# Eagle_USB_JST-XH_Converter.net
KiCad netlist of a schematic drawn in EAGLE
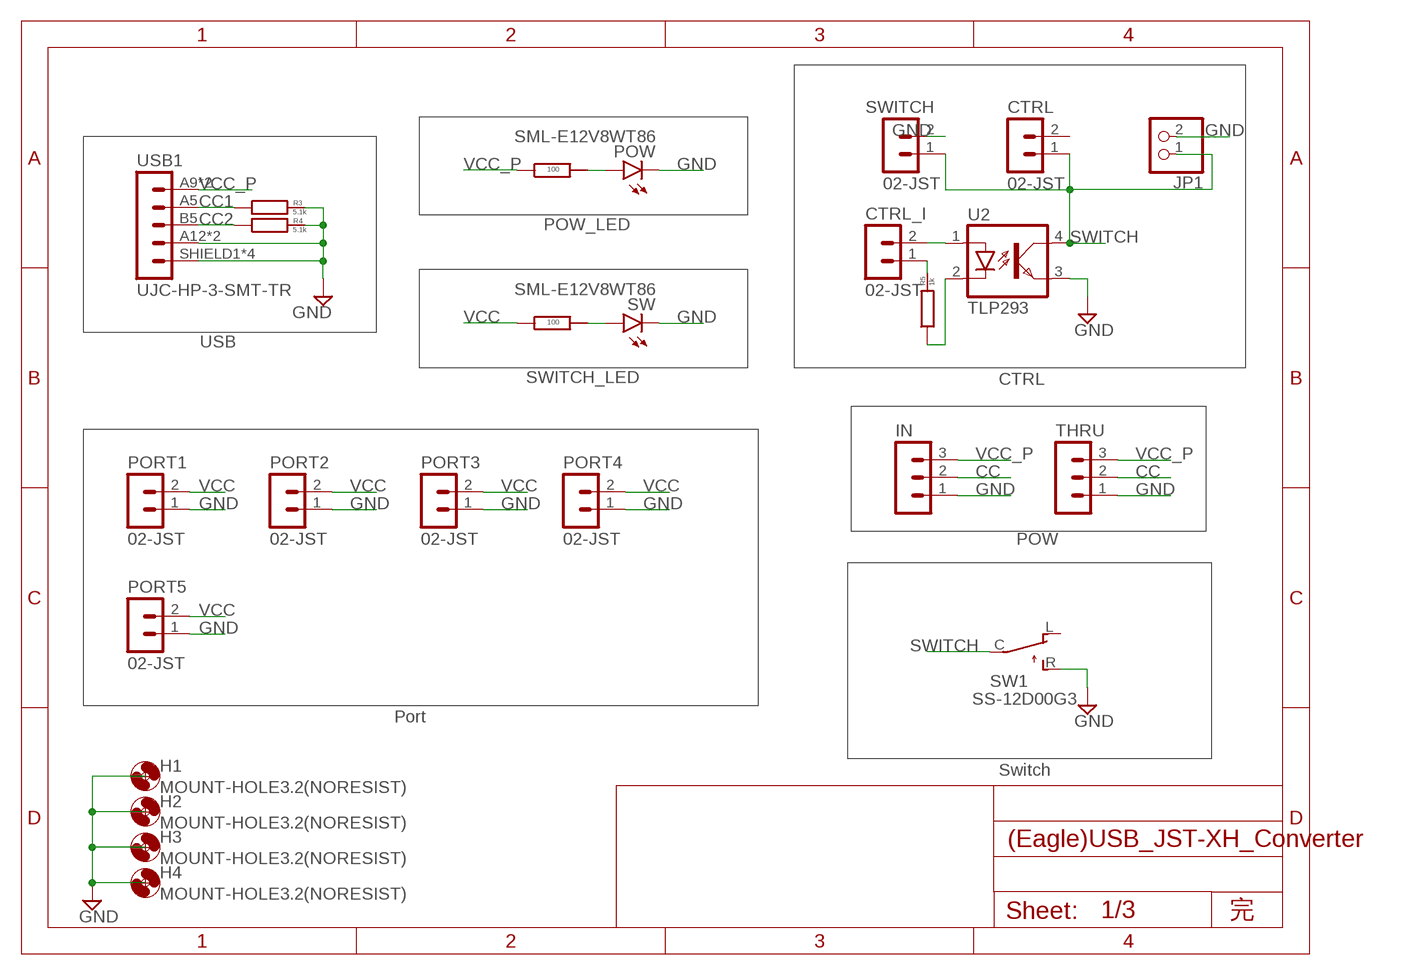
[diagram p0: schematic, sheet 1]
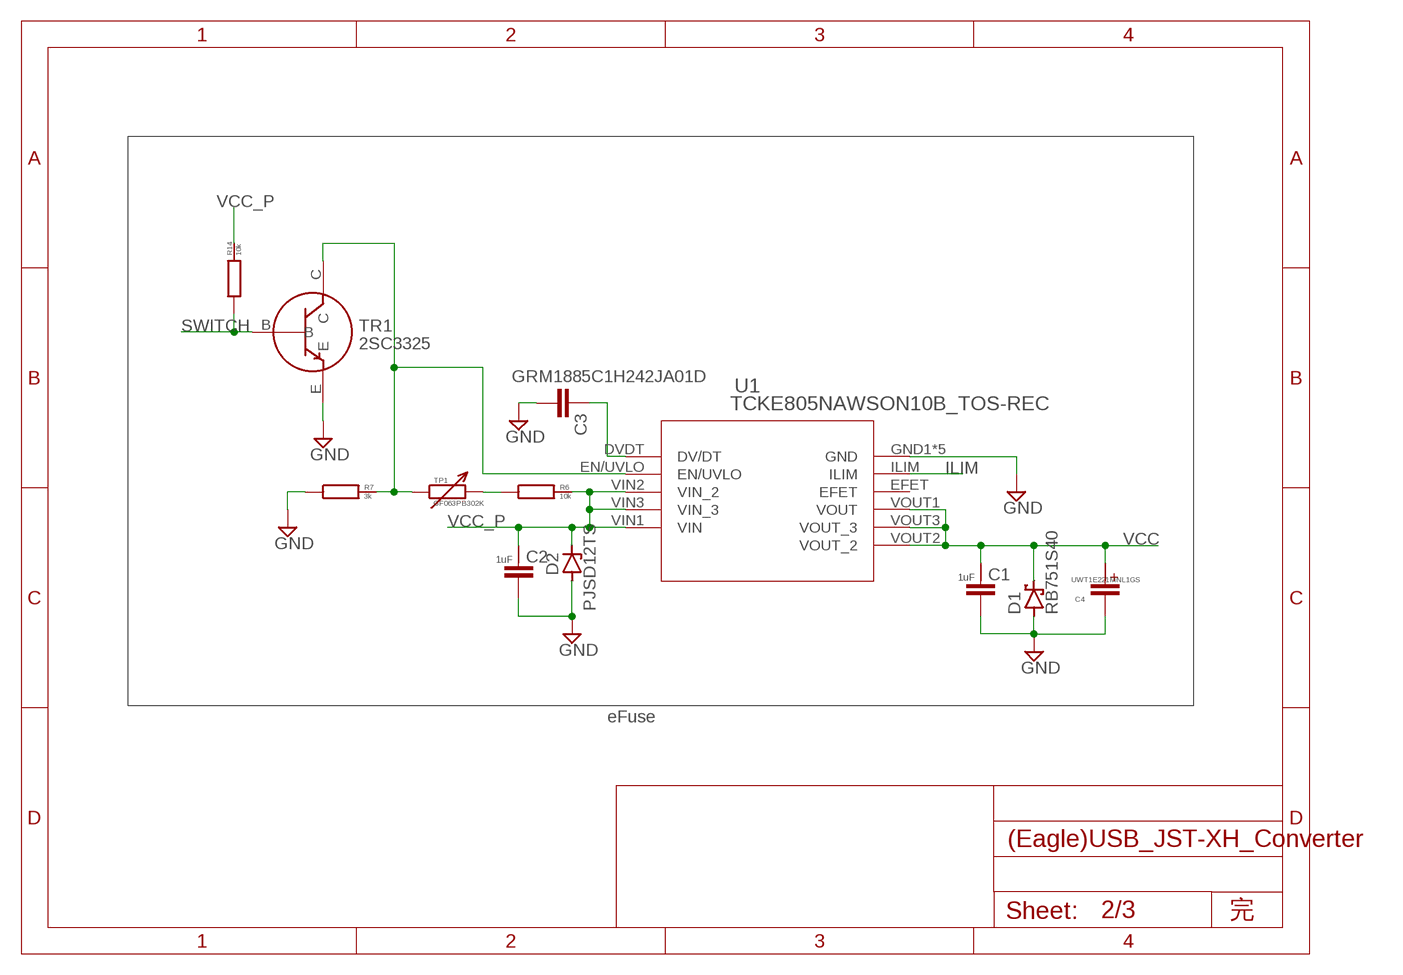
[diagram p1: schematic, sheet 2]
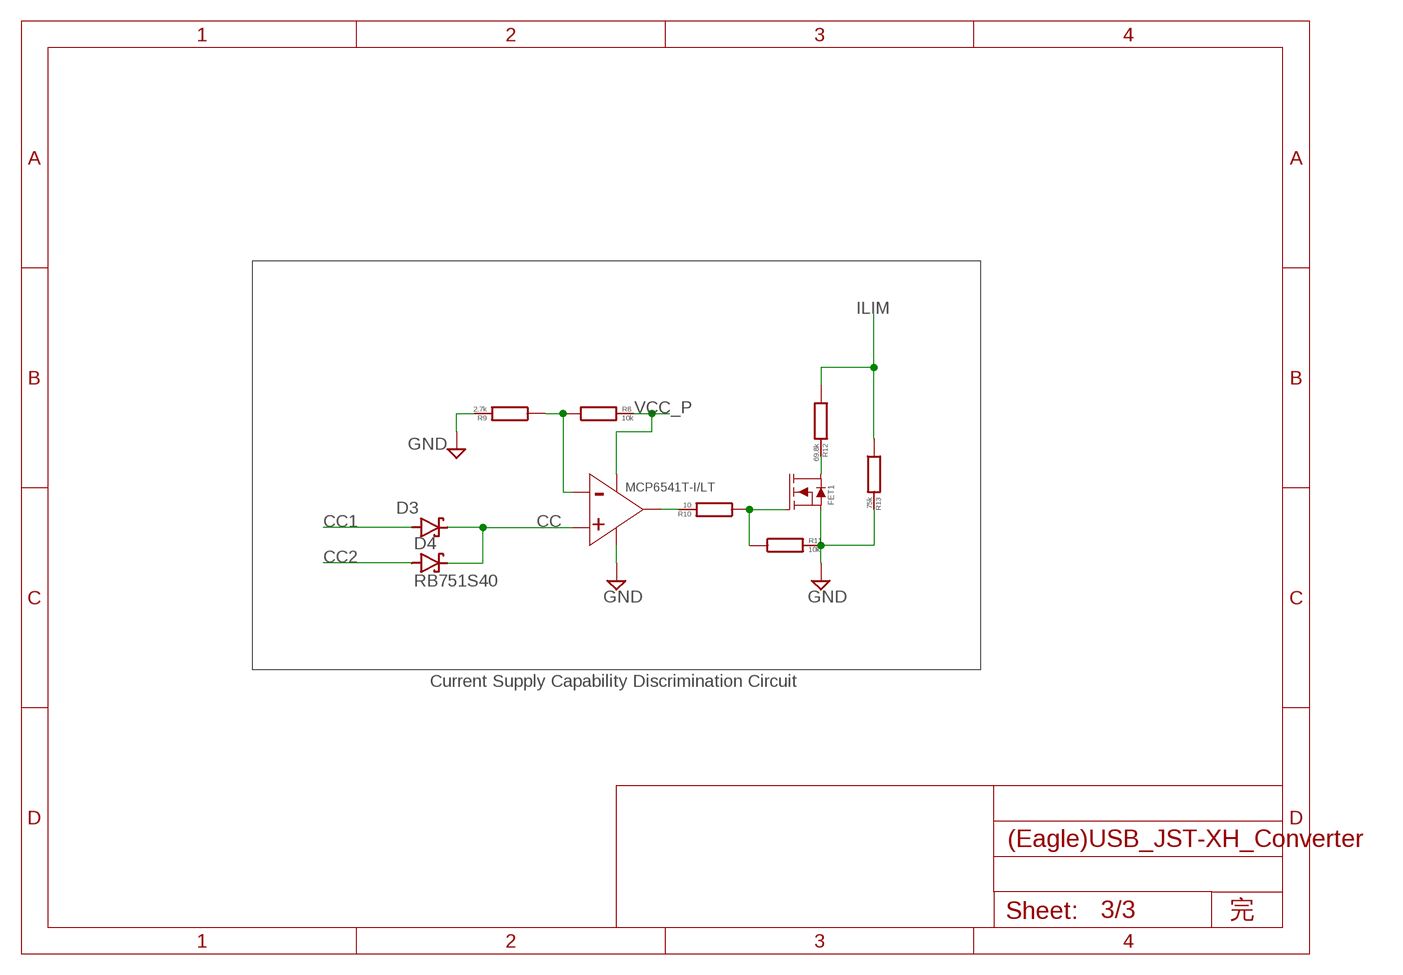
[diagram p2: schematic, sheet 3]

(export (version "E")
  (design (tool "Eeschema 10.0.6"))
  (components
    (comp (ref "COMP1")
      (value "MCP6541T-I/LT")
      (footprint "eagle-import:SC-70-5")
      (libsource (lib "eagle-import") (part "MCP6541T-I/LT"))
    )
    (comp (ref "D3")
      (value "RB751S40")
      (footprint "eagle-import:SOD-523")
      (libsource (lib "eagle-import") (part "RB751S40"))
    )
    (comp (ref "D4")
      (value "RB751S40")
      (footprint "eagle-import:SOD-523")
      (libsource (lib "eagle-import") (part "RB751S40"))
    )
    (comp (ref "FET1")
      (value "BSS138")
      (footprint "eagle-import:SOT-23")
      (libsource (lib "eagle-import") (part "BSS138"))
    )
    (comp (ref "R8")
      (value "10k")
      (footprint "eagle-import:RG2012")
      (libsource (lib "eagle-import") (part "RG2012"))
    )
    (comp (ref "R9")
      (value "2.7k")
      (footprint "eagle-import:RG2012")
      (libsource (lib "eagle-import") (part "RG2012"))
    )
    (comp (ref "R10")
      (value "10")
      (footprint "eagle-import:RG2012")
      (libsource (lib "eagle-import") (part "RG2012"))
    )
    (comp (ref "R11")
      (value "10k")
      (footprint "eagle-import:RG2012")
      (libsource (lib "eagle-import") (part "RG2012"))
    )
    (comp (ref "R12")
      (value "69.8k")
      (footprint "eagle-import:RG2012")
      (libsource (lib "eagle-import") (part "RG2012"))
    )
    (comp (ref "R13")
      (value "75k")
      (footprint "eagle-import:RG2012")
      (libsource (lib "eagle-import") (part "RG2012"))
    )
    (comp (ref "C1")
      (value "GRM21BC72A105KE01")
      (footprint "eagle-import:GRM21BC72A105KE01")
      (libsource (lib "eagle-import") (part "GRM21BC72A105KE01"))
    )
    (comp (ref "C2")
      (value "GRM21BC72A105KE01")
      (footprint "eagle-import:GRM21BC72A105KE01")
      (libsource (lib "eagle-import") (part "GRM21BC72A105KE01"))
    )
    (comp (ref "C3")
      (value "GRM1885C1H242JA01D")
      (footprint "eagle-import:GRM18")
      (libsource (lib "eagle-import") (part "GRM1885C1H242JA01D"))
    )
    (comp (ref "C4")
      (value "UWT1E221MNL1GS")
      (footprint "eagle-import:UWT1E221MNL1GS")
      (libsource (lib "eagle-import") (part "UWT1E221MNL1GS"))
    )
    (comp (ref "D1")
      (value "RB751S40")
      (footprint "eagle-import:SOD-523")
      (libsource (lib "eagle-import") (part "RB751S40"))
    )
    (comp (ref "D2")
      (value "PJSD12TS")
      (footprint "eagle-import:SOD-523")
      (libsource (lib "eagle-import") (part "PJSD12TS"))
    )
    (comp (ref "R6")
      (value "10k")
      (footprint "eagle-import:RG2012")
      (libsource (lib "eagle-import") (part "RG2012"))
    )
    (comp (ref "R7")
      (value "3k")
      (footprint "eagle-import:RG2012")
      (libsource (lib "eagle-import") (part "RG2012"))
    )
    (comp (ref "R14")
      (value "10k")
      (footprint "eagle-import:RG2012")
      (libsource (lib "eagle-import") (part "RG2012"))
    )
    (comp (ref "TP1")
      (value "GF063PB302K")
      (footprint "eagle-import:GF063PB104K")
      (libsource (lib "eagle-import") (part "GF063PB302K"))
    )
    (comp (ref "TR1")
      (value "2SC3325")
      (footprint "eagle-import:2SC3325")
      (libsource (lib "eagle-import") (part "2SC3325"))
    )
    (comp (ref "U1")
      (value "TCKE805NAWSON10B_TOS-REC")
      (footprint "eagle-import:WSON10B_TOS-RIC")
      (libsource (lib "eagle-import") (part "TCKE805NAWSON10B_TOS-REC"))
    )
    (comp (ref "CTRL")
      (value "02-JST")
      (footprint "eagle-import:B2B-XH")
      (libsource (lib "eagle-import") (part "02-JST"))
    )
    (comp (ref "CTRL_I")
      (value "02-JST")
      (footprint "eagle-import:B2B-XH")
      (libsource (lib "eagle-import") (part "02-JST"))
    )
    (comp (ref "H1")
      (value "MOUNT-HOLE3.2(NORESIST)")
      (footprint "eagle-import:3,2")
      (libsource (lib "eagle-import") (part "MOUNT-HOLE3.2(NORESIST)"))
    )
    (comp (ref "H2")
      (value "MOUNT-HOLE3.2(NORESIST)")
      (footprint "eagle-import:3,2")
      (libsource (lib "eagle-import") (part "MOUNT-HOLE3.2(NORESIST)"))
    )
    (comp (ref "H3")
      (value "MOUNT-HOLE3.2(NORESIST)")
      (footprint "eagle-import:3,2")
      (libsource (lib "eagle-import") (part "MOUNT-HOLE3.2(NORESIST)"))
    )
    (comp (ref "H4")
      (value "MOUNT-HOLE3.2(NORESIST)")
      (footprint "eagle-import:3,2")
      (libsource (lib "eagle-import") (part "MOUNT-HOLE3.2(NORESIST)"))
    )
    (comp (ref "IN")
      (value "03-JST")
      (footprint "eagle-import:B3B-XH")
      (libsource (lib "eagle-import") (part "03-JST"))
    )
    (comp (ref "JP1")
      (value "PINHD-1X2")
      (footprint "eagle-import:1X02")
      (libsource (lib "eagle-import") (part "PINHD-1X2"))
    )
    (comp (ref "PORT1")
      (value "02-JST")
      (footprint "eagle-import:B2B-XH")
      (libsource (lib "eagle-import") (part "02-JST"))
    )
    (comp (ref "PORT2")
      (value "02-JST")
      (footprint "eagle-import:B2B-XH")
      (libsource (lib "eagle-import") (part "02-JST"))
    )
    (comp (ref "PORT3")
      (value "02-JST")
      (footprint "eagle-import:B2B-XH")
      (libsource (lib "eagle-import") (part "02-JST"))
    )
    (comp (ref "PORT4")
      (value "02-JST")
      (footprint "eagle-import:B2B-XH")
      (libsource (lib "eagle-import") (part "02-JST"))
    )
    (comp (ref "PORT5")
      (value "02-JST")
      (footprint "eagle-import:B2B-XH")
      (libsource (lib "eagle-import") (part "02-JST"))
    )
    (comp (ref "POW")
      (value "SML-E12V8WT86")
      (footprint "eagle-import:SML-E12V8WT86")
      (libsource (lib "eagle-import") (part "SML-E12V8WT86"))
    )
    (comp (ref "R1")
      (value "RG2012N-101-B-T5")
      (footprint "eagle-import:RG2012")
      (libsource (lib "eagle-import") (part "RG2012N-101-B-T5"))
    )
    (comp (ref "R2")
      (value "RG2012N-101-B-T5")
      (footprint "eagle-import:RG2012")
      (libsource (lib "eagle-import") (part "RG2012N-101-B-T5"))
    )
    (comp (ref "R3")
      (value "5.1k")
      (footprint "eagle-import:RG2012")
      (libsource (lib "eagle-import") (part "RG2012"))
    )
    (comp (ref "R4")
      (value "5.1k")
      (footprint "eagle-import:RG2012")
      (libsource (lib "eagle-import") (part "RG2012"))
    )
    (comp (ref "R5")
      (value "1k")
      (footprint "eagle-import:RG2012")
      (libsource (lib "eagle-import") (part "RG2012"))
    )
    (comp (ref "SW")
      (value "SML-E12V8WT86")
      (footprint "eagle-import:SML-E12V8WT86")
      (libsource (lib "eagle-import") (part "SML-E12V8WT86"))
    )
    (comp (ref "SW1")
      (value "SS-12D00G3")
      (footprint "eagle-import:SS-12D00G3")
      (libsource (lib "eagle-import") (part "SS-12D00G3"))
    )
    (comp (ref "SWITCH")
      (value "02-JST")
      (footprint "eagle-import:B2B-XH")
      (libsource (lib "eagle-import") (part "02-JST"))
    )
    (comp (ref "THRU")
      (value "03-JST")
      (footprint "eagle-import:B3B-XH")
      (libsource (lib "eagle-import") (part "03-JST"))
    )
    (comp (ref "U2")
      (value "TLP293")
      (footprint "eagle-import:SO4_TOS")
      (fields (field (name "COPYRIGHT") "Copyright (C) 2022 Ultra Librarian. All rights reserved."))
      (libsource (lib "eagle-import") (part "TLP293"))
    )
    (comp (ref "USB1")
      (value "UJC-HP-3-SMT-TR")
      (footprint "eagle-import:UJC-HP-3-SMT-TR")
      (libsource (lib "eagle-import") (part "UJC-HP-3-SMT-TR"))
    )
  )
  (nets
    (net (code "1") (name "CC") (class "Default")
      (node (ref "COMP1") (pin "IN+") (pinfunction "IN+_IN+") (pintype "bidirectional"))
      (node (ref "D3") (pin "C") (pinfunction "C_C") (pintype "passive"))
      (node (ref "D4") (pin "C") (pinfunction "C_C") (pintype "passive"))
      (node (ref "IN") (pin "2") (pinfunction "2_2") (pintype "passive"))
      (node (ref "THRU") (pin "2") (pinfunction "2_2") (pintype "passive"))
    )
    (net (code "2") (name "CC1") (class "Default")
      (node (ref "D3") (pin "A") (pinfunction "A_A") (pintype "passive"))
      (node (ref "R3") (pin "LEFT") (pinfunction "LEFT_LEFT") (pintype "bidirectional"))
      (node (ref "USB1") (pin "A5") (pinfunction "CC1_A5") (pintype "passive"))
    )
    (net (code "3") (name "CC2") (class "Default")
      (node (ref "D4") (pin "A") (pinfunction "A_A") (pintype "passive"))
      (node (ref "R4") (pin "LEFT") (pinfunction "LEFT_LEFT") (pintype "bidirectional"))
      (node (ref "USB1") (pin "B5") (pinfunction "CC2_B5") (pintype "passive"))
    )
    (net (code "4") (name "GND") (class "Default")
      (node (ref "C1") (pin "P$2") (pinfunction "P$2_P$2") (pintype "bidirectional"))
      (node (ref "C2") (pin "P$2") (pinfunction "P$2_P$2") (pintype "bidirectional"))
      (node (ref "C3") (pin "R") (pinfunction "2_R") (pintype "passive"))
      (node (ref "C4") (pin "C") (pinfunction "CATHODE_C") (pintype "bidirectional"))
      (node (ref "COMP1") (pin "VSS") (pinfunction "VSS_VSS") (pintype "bidirectional"))
      (node (ref "D1") (pin "A") (pinfunction "A_A") (pintype "passive"))
      (node (ref "D2") (pin "A") (pinfunction "A_A") (pintype "passive"))
      (node (ref "FET1") (pin "S") (pinfunction "S_S") (pintype "passive"))
      (node (ref "H1") (pin "P$1") (pinfunction "P$1_P$1") (pintype "bidirectional"))
      (node (ref "H2") (pin "P$1") (pinfunction "P$1_P$1") (pintype "bidirectional"))
      (node (ref "H3") (pin "P$1") (pinfunction "P$1_P$1") (pintype "bidirectional"))
      (node (ref "H4") (pin "P$1") (pinfunction "P$1_P$1") (pintype "bidirectional"))
      (node (ref "IN") (pin "1") (pinfunction "1_1") (pintype "passive"))
      (node (ref "JP1") (pin "2") (pinfunction "2_2") (pintype "passive"))
      (node (ref "PORT1") (pin "1") (pinfunction "1_1") (pintype "passive"))
      (node (ref "PORT2") (pin "1") (pinfunction "1_1") (pintype "passive"))
      (node (ref "PORT3") (pin "1") (pinfunction "1_1") (pintype "passive"))
      (node (ref "PORT4") (pin "1") (pinfunction "1_1") (pintype "passive"))
      (node (ref "PORT5") (pin "1") (pinfunction "1_1") (pintype "passive"))
      (node (ref "POW") (pin "K") (pinfunction "C_K") (pintype "passive"))
      (node (ref "R11") (pin "RIGHT") (pinfunction "RIGHT_RIGHT") (pintype "bidirectional"))
      (node (ref "R13") (pin "RIGHT") (pinfunction "RIGHT_RIGHT") (pintype "bidirectional"))
      (node (ref "R3") (pin "RIGHT") (pinfunction "RIGHT_RIGHT") (pintype "bidirectional"))
      (node (ref "R4") (pin "RIGHT") (pinfunction "RIGHT_RIGHT") (pintype "bidirectional"))
      (node (ref "R7") (pin "LEFT") (pinfunction "LEFT_LEFT") (pintype "bidirectional"))
      (node (ref "R9") (pin "RIGHT") (pinfunction "RIGHT_RIGHT") (pintype "bidirectional"))
      (node (ref "SW") (pin "K") (pinfunction "C_K") (pintype "passive"))
      (node (ref "SW1") (pin "R") (pinfunction "R_R") (pintype "passive"))
      (node (ref "SWITCH") (pin "2") (pinfunction "2_2") (pintype "passive"))
      (node (ref "THRU") (pin "1") (pinfunction "1_1") (pintype "passive"))
      (node (ref "TR1") (pin "E") (pinfunction "E_E") (pintype "bidirectional"))
      (node (ref "U1") (pin "GND1") (pinfunction "GND_GND1") (pintype "passive"))
      (node (ref "U1") (pin "GND2") (pinfunction "GND_GND2") (pintype "passive"))
      (node (ref "U1") (pin "GND3") (pinfunction "GND_GND3") (pintype "passive"))
      (node (ref "U1") (pin "GND4") (pinfunction "GND_GND4") (pintype "passive"))
      (node (ref "U1") (pin "GND5") (pinfunction "GND_GND5") (pintype "passive"))
      (node (ref "U2") (pin "3") (pinfunction "3_3") (pintype "passive"))
      (node (ref "USB1") (pin "A12") (pinfunction "GND_A12") (pintype "passive"))
      (node (ref "USB1") (pin "B12") (pinfunction "GND_B12") (pintype "passive"))
      (node (ref "USB1") (pin "SHIELD1") (pinfunction "SHIELD_SHIELD1") (pintype "passive"))
      (node (ref "USB1") (pin "SHIELD2") (pinfunction "SHIELD_SHIELD2") (pintype "passive"))
      (node (ref "USB1") (pin "SHIELD3") (pinfunction "SHIELD_SHIELD3") (pintype "passive"))
      (node (ref "USB1") (pin "SHIELD4") (pinfunction "SHIELD_SHIELD4") (pintype "passive"))
    )
    (net (code "5") (name "ILIM") (class "Default")
      (node (ref "R12") (pin "LEFT") (pinfunction "LEFT_LEFT") (pintype "bidirectional"))
      (node (ref "R13") (pin "LEFT") (pinfunction "LEFT_LEFT") (pintype "bidirectional"))
      (node (ref "U1") (pin "ILIM") (pinfunction "ILIM_ILIM") (pintype "input"))
    )
    (net (code "6") (name "Net-(C3-1)") (class "Default")
      (node (ref "C3") (pin "L") (pinfunction "1_L") (pintype "passive"))
      (node (ref "U1") (pin "DVDT") (pinfunction "DV/DT_DVDT") (pintype "input"))
    )
    (net (code "7") (name "Net-(COMP1-PadIN-)") (class "Default")
      (node (ref "COMP1") (pin "IN-") (pinfunction "IN-_IN-") (pintype "bidirectional"))
      (node (ref "R8") (pin "LEFT") (pinfunction "LEFT_LEFT") (pintype "bidirectional"))
      (node (ref "R9") (pin "LEFT") (pinfunction "LEFT_LEFT") (pintype "bidirectional"))
    )
    (net (code "8") (name "Net-(COMP1-PadOUT)") (class "Default")
      (node (ref "COMP1") (pin "OUT") (pinfunction "OUT_OUT") (pintype "bidirectional"))
      (node (ref "R10") (pin "RIGHT") (pinfunction "RIGHT_RIGHT") (pintype "bidirectional"))
    )
    (net (code "9") (name "Net-(CTRL_I-Pad1)") (class "Default")
      (node (ref "CTRL_I") (pin "1") (pinfunction "1_1") (pintype "passive"))
      (node (ref "R5") (pin "RIGHT") (pinfunction "RIGHT_RIGHT") (pintype "bidirectional"))
    )
    (net (code "10") (name "Net-(CTRL_I-Pad2)") (class "Default")
      (node (ref "CTRL_I") (pin "2") (pinfunction "2_2") (pintype "passive"))
      (node (ref "U2") (pin "1") (pinfunction "1_1") (pintype "passive"))
    )
    (net (code "11") (name "Net-(FET1-PadD)") (class "Default")
      (node (ref "FET1") (pin "D") (pinfunction "D_D") (pintype "passive"))
      (node (ref "R12") (pin "RIGHT") (pinfunction "RIGHT_RIGHT") (pintype "bidirectional"))
    )
    (net (code "12") (name "Net-(FET1-PadG)") (class "Default")
      (node (ref "FET1") (pin "G") (pinfunction "G_G") (pintype "passive"))
      (node (ref "R10") (pin "LEFT") (pinfunction "LEFT_LEFT") (pintype "bidirectional"))
      (node (ref "R11") (pin "LEFT") (pinfunction "LEFT_LEFT") (pintype "bidirectional"))
    )
    (net (code "13") (name "Net-(R1-P$1)") (class "Default")
      (node (ref "POW") (pin "A") (pinfunction "A_A") (pintype "passive"))
      (node (ref "R1") (pin "LEFT") (pinfunction "P$1_LEFT") (pintype "bidirectional"))
    )
    (net (code "14") (name "Net-(R2-P$1)") (class "Default")
      (node (ref "R2") (pin "LEFT") (pinfunction "P$1_LEFT") (pintype "bidirectional"))
      (node (ref "SW") (pin "A") (pinfunction "A_A") (pintype "passive"))
    )
    (net (code "15") (name "Net-(R5-PadLEFT)") (class "Default")
      (node (ref "R5") (pin "LEFT") (pinfunction "LEFT_LEFT") (pintype "bidirectional"))
      (node (ref "U2") (pin "2") (pinfunction "2_2") (pintype "passive"))
    )
    (net (code "16") (name "Net-(R6-PadLEFT)") (class "Default")
      (node (ref "R6") (pin "LEFT") (pinfunction "LEFT_LEFT") (pintype "bidirectional"))
      (node (ref "TP1") (pin "CENTER") (pinfunction "RIGHT_CENTER") (pintype "passive"))
      (node (ref "TP1") (pin "RIGHT") (pinfunction "RIGHT_RIGHT") (pintype "passive"))
    )
    (net (code "17") (name "Net-(R7-PadRIGHT)") (class "Default")
      (node (ref "R7") (pin "RIGHT") (pinfunction "RIGHT_RIGHT") (pintype "bidirectional"))
      (node (ref "TP1") (pin "LEFT") (pinfunction "LEFT_LEFT") (pintype "passive"))
      (node (ref "TR1") (pin "C") (pinfunction "C_C") (pintype "bidirectional"))
      (node (ref "U1") (pin "EN/UVLO") (pinfunction "EN/UVLO_EN/UVLO") (pintype "passive"))
    )
    (net (code "18") (name "SWITCH") (class "Default")
      (node (ref "CTRL") (pin "1") (pinfunction "1_1") (pintype "passive"))
      (node (ref "JP1") (pin "1") (pinfunction "1_1") (pintype "passive"))
      (node (ref "R14") (pin "LEFT") (pinfunction "LEFT_LEFT") (pintype "bidirectional"))
      (node (ref "SW1") (pin "C") (pinfunction "C_C") (pintype "passive"))
      (node (ref "SWITCH") (pin "1") (pinfunction "1_1") (pintype "passive"))
      (node (ref "TR1") (pin "B") (pinfunction "B_B") (pintype "bidirectional"))
      (node (ref "U2") (pin "4") (pinfunction "4_4") (pintype "passive"))
    )
    (net (code "19") (name "VCC") (class "Default")
      (node (ref "C1") (pin "P$1") (pinfunction "P$1_P$1") (pintype "bidirectional"))
      (node (ref "C4") (pin "A") (pinfunction "ANODE_A") (pintype "bidirectional"))
      (node (ref "D1") (pin "C") (pinfunction "C_C") (pintype "passive"))
      (node (ref "PORT1") (pin "2") (pinfunction "2_2") (pintype "passive"))
      (node (ref "PORT2") (pin "2") (pinfunction "2_2") (pintype "passive"))
      (node (ref "PORT3") (pin "2") (pinfunction "2_2") (pintype "passive"))
      (node (ref "PORT4") (pin "2") (pinfunction "2_2") (pintype "passive"))
      (node (ref "PORT5") (pin "2") (pinfunction "2_2") (pintype "passive"))
      (node (ref "R2") (pin "RIGHT") (pinfunction "P$2_RIGHT") (pintype "bidirectional"))
      (node (ref "U1") (pin "VOUT1") (pinfunction "VOUT_VOUT1") (pintype "bidirectional"))
      (node (ref "U1") (pin "VOUT2") (pinfunction "VOUT_2_VOUT2") (pintype "bidirectional"))
      (node (ref "U1") (pin "VOUT3") (pinfunction "VOUT_3_VOUT3") (pintype "bidirectional"))
    )
    (net (code "20") (name "VCC_P") (class "Default")
      (node (ref "C2") (pin "P$1") (pinfunction "P$1_P$1") (pintype "bidirectional"))
      (node (ref "COMP1") (pin "VDD") (pinfunction "VDD_VDD") (pintype "bidirectional"))
      (node (ref "D2") (pin "C") (pinfunction "C_C") (pintype "passive"))
      (node (ref "IN") (pin "3") (pinfunction "3_3") (pintype "passive"))
      (node (ref "R1") (pin "RIGHT") (pinfunction "P$2_RIGHT") (pintype "bidirectional"))
      (node (ref "R14") (pin "RIGHT") (pinfunction "RIGHT_RIGHT") (pintype "bidirectional"))
      (node (ref "R6") (pin "RIGHT") (pinfunction "RIGHT_RIGHT") (pintype "bidirectional"))
      (node (ref "R8") (pin "RIGHT") (pinfunction "RIGHT_RIGHT") (pintype "bidirectional"))
      (node (ref "THRU") (pin "3") (pinfunction "3_3") (pintype "passive"))
      (node (ref "U1") (pin "VIN1") (pinfunction "VIN_VIN1") (pintype "input"))
      (node (ref "U1") (pin "VIN2") (pinfunction "VIN_2_VIN2") (pintype "input"))
      (node (ref "U1") (pin "VIN3") (pinfunction "VIN_3_VIN3") (pintype "input"))
      (node (ref "USB1") (pin "A9") (pinfunction "V-BUS_A9") (pintype "passive"))
      (node (ref "USB1") (pin "B9") (pinfunction "V-BUS_B9") (pintype "passive"))
    )
    (net (code "21") (name "unconnected-(CTRL-Pad2)") (class "Default")
      (node (ref "CTRL") (pin "2") (pinfunction "2_2") (pintype "passive"))
    )
    (net (code "22") (name "unconnected-(SW1-PadL)") (class "Default")
      (node (ref "SW1") (pin "L") (pinfunction "L_L") (pintype "passive"))
    )
    (net (code "23") (name "unconnected-(U1-PadEFET)") (class "Default")
      (node (ref "U1") (pin "EFET") (pinfunction "EFET_EFET") (pintype "passive"))
    )
  )
)
